# BMS_Rev2_logic_B.net
KiCad netlist of a schematic drawn in EAGLE
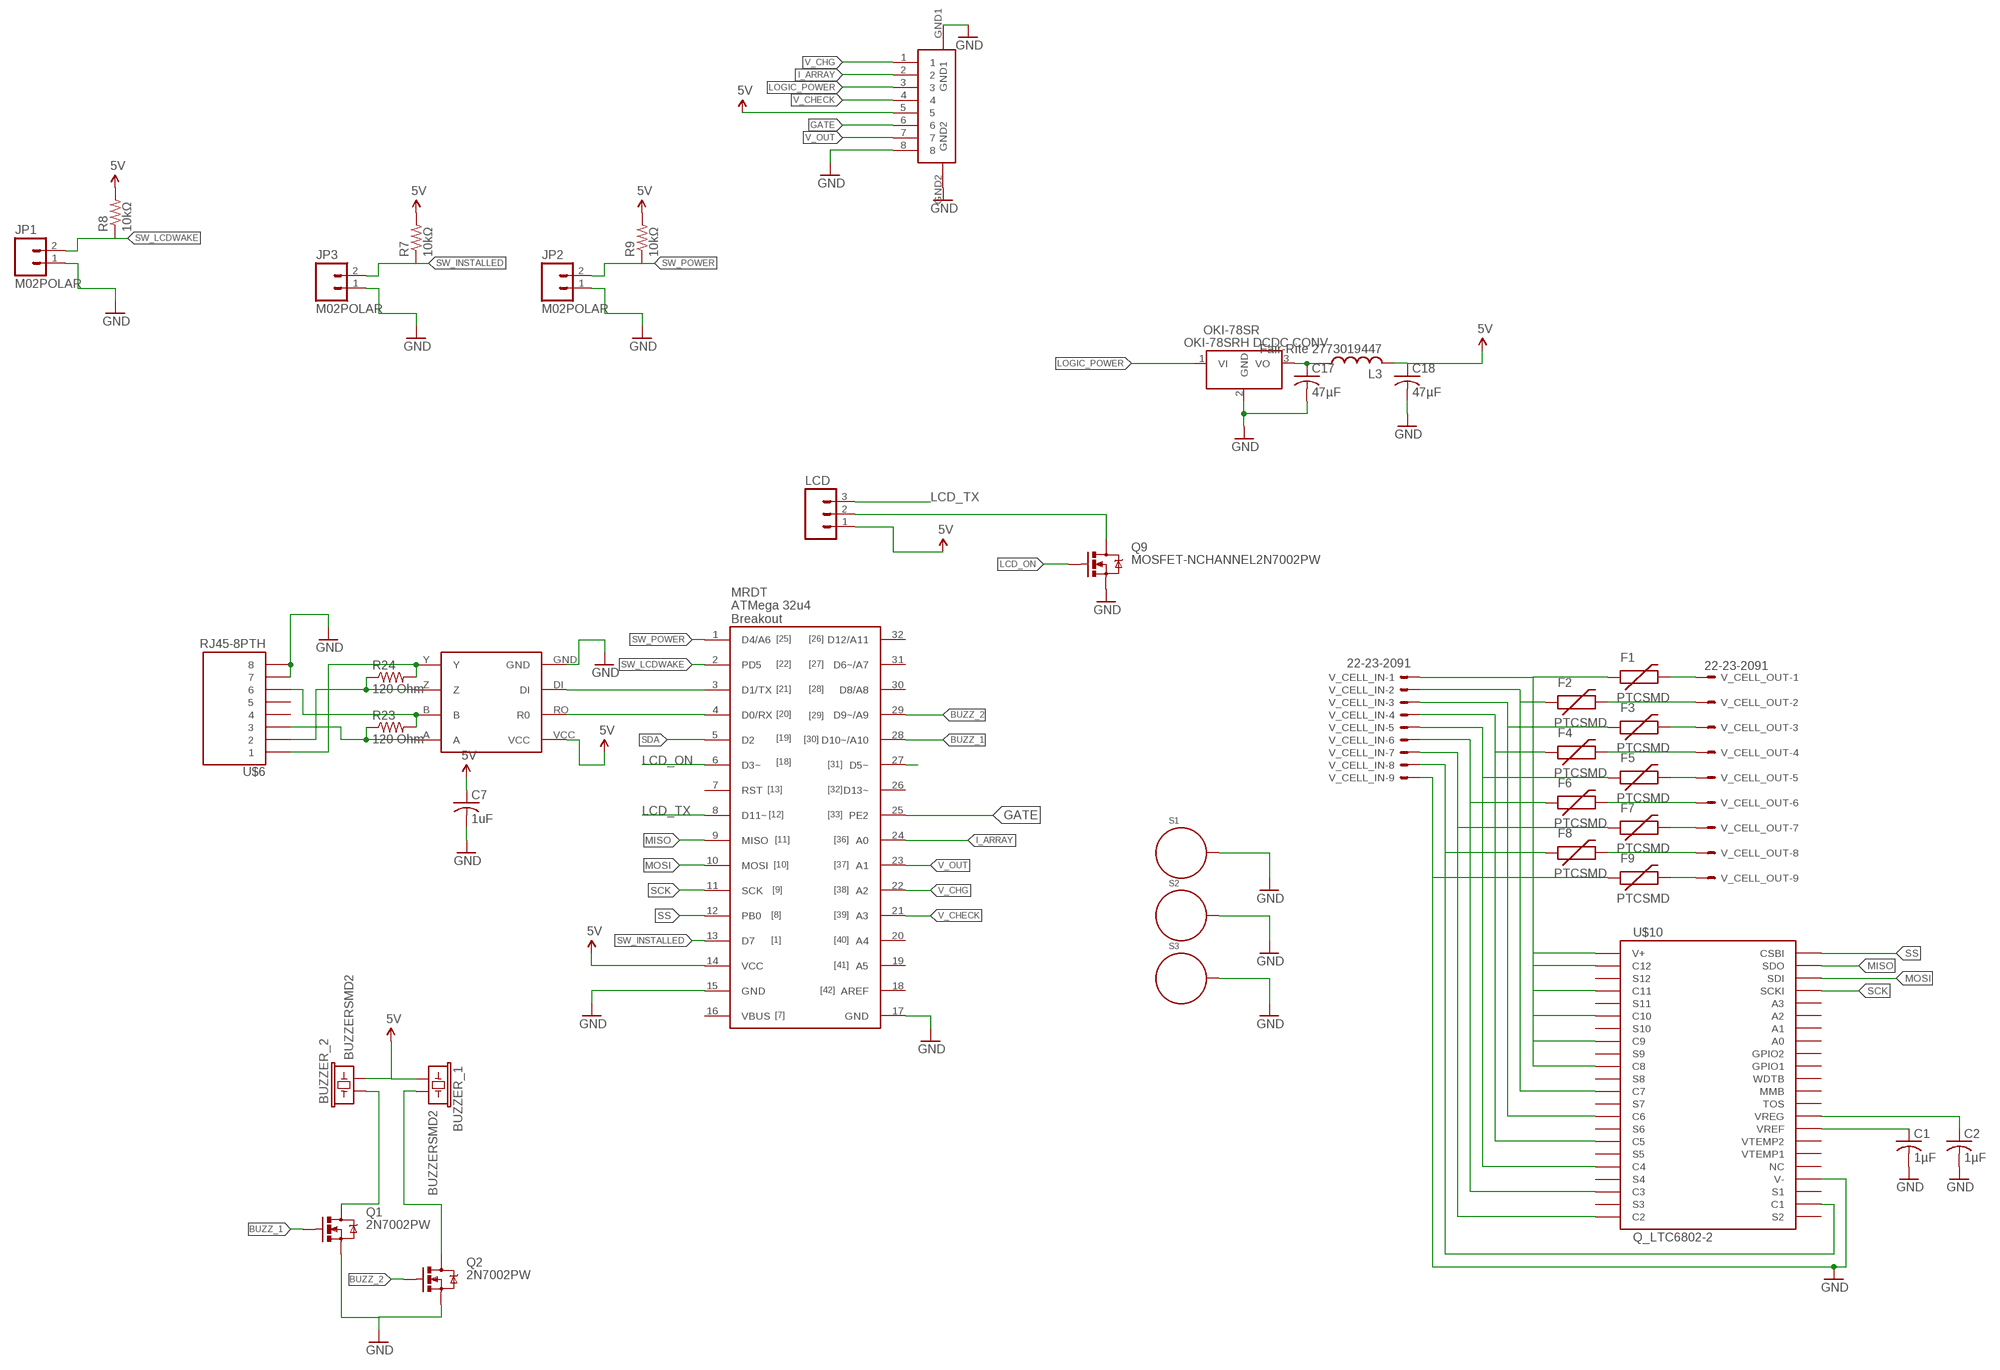
[diagram p0: schematic, sheet 1]

(export (version "E")
  (design (tool "Eeschema 10.0.6"))
  (components
    (comp (ref "BUZZER_1")
      (value "BUZZERSMD2")
      (footprint "eagle-import:BUZZER-CCV")
      (libsource (lib "eagle-import") (part "BUZZERSMD2"))
    )
    (comp (ref "BUZZER_2")
      (value "BUZZERSMD2")
      (footprint "eagle-import:BUZZER-CCV")
      (libsource (lib "eagle-import") (part "BUZZERSMD2"))
    )
    (comp (ref "C1")
      (value "1µF")
      (footprint "eagle-import:C1206")
      (libsource (lib "eagle-import") (part "C-USC1206"))
    )
    (comp (ref "C2")
      (value "1µF")
      (footprint "eagle-import:C1206")
      (libsource (lib "eagle-import") (part "C-USC1206"))
    )
    (comp (ref "C7")
      (value "1uF")
      (footprint "eagle-import:C1206")
      (libsource (lib "eagle-import") (part "C-USC1206"))
    )
    (comp (ref "C17")
      (value "47µF")
      (footprint "eagle-import:C1206")
      (libsource (lib "eagle-import") (part "C-USC1206"))
    )
    (comp (ref "C18")
      (value "47µF")
      (footprint "eagle-import:C1206")
      (libsource (lib "eagle-import") (part "C-USC1206"))
    )
    (comp (ref "F1")
      (value "PTCSMD")
      (footprint "eagle-import:PTC-1206")
      (libsource (lib "eagle-import") (part "PTCSMD"))
    )
    (comp (ref "F2")
      (value "PTCSMD")
      (footprint "eagle-import:PTC-1206")
      (libsource (lib "eagle-import") (part "PTCSMD"))
    )
    (comp (ref "F3")
      (value "PTCSMD")
      (footprint "eagle-import:PTC-1206")
      (libsource (lib "eagle-import") (part "PTCSMD"))
    )
    (comp (ref "F4")
      (value "PTCSMD")
      (footprint "eagle-import:PTC-1206")
      (libsource (lib "eagle-import") (part "PTCSMD"))
    )
    (comp (ref "F5")
      (value "PTCSMD")
      (footprint "eagle-import:PTC-1206")
      (libsource (lib "eagle-import") (part "PTCSMD"))
    )
    (comp (ref "F6")
      (value "PTCSMD")
      (footprint "eagle-import:PTC-1206")
      (libsource (lib "eagle-import") (part "PTCSMD"))
    )
    (comp (ref "F7")
      (value "PTCSMD")
      (footprint "eagle-import:PTC-1206")
      (libsource (lib "eagle-import") (part "PTCSMD"))
    )
    (comp (ref "F8")
      (value "PTCSMD")
      (footprint "eagle-import:PTC-1206")
      (libsource (lib "eagle-import") (part "PTCSMD"))
    )
    (comp (ref "F9")
      (value "PTCSMD")
      (footprint "eagle-import:PTC-1206")
      (libsource (lib "eagle-import") (part "PTCSMD"))
    )
    (comp (ref "JP1")
      (value "M02POLAR")
      (footprint "eagle-import:MOLEX-1X2")
      (libsource (lib "eagle-import") (part "M02POLAR"))
    )
    (comp (ref "JP2")
      (value "M02POLAR")
      (footprint "eagle-import:MOLEX-1X2")
      (libsource (lib "eagle-import") (part "M02POLAR"))
    )
    (comp (ref "JP3")
      (value "M02POLAR")
      (footprint "eagle-import:MOLEX-1X2")
      (libsource (lib "eagle-import") (part "M02POLAR"))
    )
    (comp (ref "L3")
      (value "Fair-Rite 2773019447")
      (footprint "eagle-import:L4532M")
      (libsource (lib "eagle-import") (part "L-USL4532C"))
    )
    (comp (ref "LCD")
      (value "M03POLAR")
      (footprint "eagle-import:MOLEX-1X3")
      (libsource (lib "eagle-import") (part "M03POLAR"))
    )
    (comp (ref "OKI-78SR")
      (value "Q_OKI-78SR")
      (footprint "eagle-import:OKI-78SRH")
      (libsource (lib "eagle-import") (part "Q_OKI-78SR"))
    )
    (comp (ref "Q1")
      (value "2N7002PW")
      (footprint "eagle-import:SOT323")
      (libsource (lib "eagle-import") (part "MOSFET-NCHANNEL2N7002PW"))
    )
    (comp (ref "Q2")
      (value "2N7002PW")
      (footprint "eagle-import:SOT323")
      (libsource (lib "eagle-import") (part "MOSFET-NCHANNEL2N7002PW"))
    )
    (comp (ref "Q9")
      (value "MOSFET-NCHANNEL2N7002PW")
      (footprint "eagle-import:SOT323")
      (libsource (lib "eagle-import") (part "MOSFET-NCHANNEL2N7002PW"))
    )
    (comp (ref "R7")
      (value "10kΩ")
      (footprint "eagle-import:R1206")
      (libsource (lib "eagle-import") (part "R-US_R1206"))
    )
    (comp (ref "R8")
      (value "10kΩ")
      (footprint "eagle-import:R1206")
      (libsource (lib "eagle-import") (part "R-US_R1206"))
    )
    (comp (ref "R9")
      (value "10kΩ")
      (footprint "eagle-import:R1206")
      (libsource (lib "eagle-import") (part "R-US_R1206"))
    )
    (comp (ref "R23")
      (value "120 Ohm")
      (footprint "eagle-import:1206")
      (libsource (lib "eagle-import") (part "RESISTOR1206"))
    )
    (comp (ref "R24")
      (value "120 Ohm")
      (footprint "eagle-import:1206")
      (libsource (lib "eagle-import") (part "RESISTOR1206"))
    )
    (comp (ref "S1")
      (value "STANDOFF_ELECTRICAL")
      (footprint "eagle-import:STANDOFF-ELECTRICAL")
      (libsource (lib "eagle-import") (part "STANDOFF_ELECTRICAL"))
    )
    (comp (ref "S2")
      (value "STANDOFF_ELECTRICAL")
      (footprint "eagle-import:STANDOFF-ELECTRICAL")
      (libsource (lib "eagle-import") (part "STANDOFF_ELECTRICAL"))
    )
    (comp (ref "S3")
      (value "STANDOFF_ELECTRICAL")
      (footprint "eagle-import:STANDOFF-ELECTRICAL")
      (libsource (lib "eagle-import") (part "STANDOFF_ELECTRICAL"))
    )
    (comp (ref "U$1")
      (value "8POS_LOGIC")
      (footprint "eagle-import:LOGIC_CONNECT")
      (libsource (lib "eagle-import") (part "8POS_LOGIC"))
    )
    (comp (ref "U$3")
      (value "32U4_BREAKOUT")
      (footprint "eagle-import:32U4_MCU_DIP")
      (libsource (lib "eagle-import") (part "32U4_BREAKOUT"))
    )
    (comp (ref "U$6")
      (value "RJ45-8PTH")
      (footprint "eagle-import:RJ45-8")
      (libsource (lib "eagle-import") (part "RJ45-8PTH"))
    )
    (comp (ref "U$9")
      (value "MAX3077")
      (footprint "eagle-import:MAX3070E")
      (libsource (lib "eagle-import") (part "MAX3077"))
    )
    (comp (ref "U$10")
      (value "Q_LTC6802-2")
      (footprint "eagle-import:SSOP44")
      (libsource (lib "eagle-import") (part "Q_LTC6802-2"))
    )
    (comp (ref "V_CELL_IN")
      (value "22-23-2091")
      (footprint "eagle-import:22-23-2091")
      (fields (field (name "MF") "MOLEX"))
      (libsource (lib "eagle-import") (part "22-23-2091"))
    )
    (comp (ref "V_CELL_OUT")
      (value "22-23-2091")
      (footprint "eagle-import:22-23-2091")
      (fields (field (name "MF") "MOLEX"))
      (libsource (lib "eagle-import") (part "22-23-2091"))
    )
  )
  (nets
    (net (code "1") (name "/LCD_TX") (class "Default")
      (node (ref "LCD") (pin "3") (pinfunction "3_3") (pintype "passive"))
      (node (ref "U$3") (pin "8") (pinfunction "D11~{}_8") (pintype "bidirectional"))
    )
    (net (code "2") (name "5V") (class "Default")
      (node (ref "BUZZER_1") (pin "+") (pinfunction "1_+") (pintype "passive"))
      (node (ref "BUZZER_2") (pin "-") (pinfunction "2_-") (pintype "passive"))
      (node (ref "C18") (pin "1") (pinfunction "1_1") (pintype "passive"))
      (node (ref "C7") (pin "1") (pinfunction "1_1") (pintype "passive"))
      (node (ref "L3") (pin "2") (pinfunction "2_2") (pintype "passive"))
      (node (ref "LCD") (pin "1") (pinfunction "1_1") (pintype "passive"))
      (node (ref "R7") (pin "2") (pinfunction "2_2") (pintype "passive"))
      (node (ref "R8") (pin "2") (pinfunction "2_2") (pintype "passive"))
      (node (ref "R9") (pin "2") (pinfunction "2_2") (pintype "passive"))
      (node (ref "U$1") (pin "5") (pinfunction "5_5") (pintype "bidirectional"))
      (node (ref "U$3") (pin "14") (pinfunction "VCC_14") (pintype "bidirectional"))
      (node (ref "U$9") (pin "VCC") (pinfunction "VCC_VCC") (pintype "bidirectional"))
    )
    (net (code "3") (name "BUZZ_1") (class "Default")
      (node (ref "Q1") (pin "1") (pinfunction "G_1") (pintype "passive"))
      (node (ref "U$3") (pin "28") (pinfunction "D10~{/A10}_28") (pintype "bidirectional"))
    )
    (net (code "4") (name "BUZZ_2") (class "Default")
      (node (ref "Q2") (pin "1") (pinfunction "G_1") (pintype "passive"))
      (node (ref "U$3") (pin "29") (pinfunction "D9~{/A9}_29") (pintype "bidirectional"))
    )
    (net (code "5") (name "GATE") (class "Default")
      (node (ref "U$1") (pin "6") (pinfunction "6_6") (pintype "bidirectional"))
      (node (ref "U$3") (pin "25") (pinfunction "PE2_25") (pintype "bidirectional"))
    )
    (net (code "6") (name "GND") (class "Default")
      (node (ref "C1") (pin "2") (pinfunction "2_2") (pintype "passive"))
      (node (ref "C17") (pin "2") (pinfunction "2_2") (pintype "passive"))
      (node (ref "C18") (pin "2") (pinfunction "2_2") (pintype "passive"))
      (node (ref "C2") (pin "2") (pinfunction "2_2") (pintype "passive"))
      (node (ref "C7") (pin "2") (pinfunction "2_2") (pintype "passive"))
      (node (ref "F9") (pin "1") (pinfunction "1_1") (pintype "bidirectional"))
      (node (ref "JP1") (pin "1") (pinfunction "1_1") (pintype "passive"))
      (node (ref "JP2") (pin "1") (pinfunction "1_1") (pintype "passive"))
      (node (ref "JP3") (pin "1") (pinfunction "1_1") (pintype "passive"))
      (node (ref "OKI-78SR") (pin "2") (pinfunction "GND_2") (pintype "bidirectional"))
      (node (ref "Q1") (pin "2") (pinfunction "S_2") (pintype "passive"))
      (node (ref "Q2") (pin "2") (pinfunction "S_2") (pintype "passive"))
      (node (ref "Q9") (pin "2") (pinfunction "S_2") (pintype "passive"))
      (node (ref "S1") (pin "P1") (pinfunction "P$1_P1") (pintype "bidirectional"))
      (node (ref "S2") (pin "P1") (pinfunction "P$1_P1") (pintype "bidirectional"))
      (node (ref "S3") (pin "P1") (pinfunction "P$1_P1") (pintype "bidirectional"))
      (node (ref "U$1") (pin "8") (pinfunction "8_8") (pintype "bidirectional"))
      (node (ref "U$1") (pin "GND1") (pinfunction "GND1_GND1") (pintype "bidirectional"))
      (node (ref "U$1") (pin "GND2") (pinfunction "GND2_GND2") (pintype "bidirectional"))
      (node (ref "U$10") (pin "26") (pinfunction "V-_26") (pintype "bidirectional"))
      (node (ref "U$3") (pin "15") (pinfunction "GND_15") (pintype "bidirectional"))
      (node (ref "U$3") (pin "17") (pinfunction "GND_17") (pintype "bidirectional"))
      (node (ref "U$6") (pin "7") (pinfunction "7_7") (pintype "bidirectional"))
      (node (ref "U$6") (pin "8") (pinfunction "8_8") (pintype "bidirectional"))
      (node (ref "U$9") (pin "GND") (pinfunction "GND_GND") (pintype "bidirectional"))
      (node (ref "V_CELL_IN") (pin "9") (pinfunction "S_9") (pintype "passive"))
    )
    (net (code "7") (name "I_ARRAY") (class "Default")
      (node (ref "U$1") (pin "2") (pinfunction "2_2") (pintype "bidirectional"))
      (node (ref "U$3") (pin "24") (pinfunction "A0_24") (pintype "bidirectional"))
    )
    (net (code "8") (name "LCD_ON") (class "Default")
      (node (ref "Q9") (pin "1") (pinfunction "G_1") (pintype "passive"))
      (node (ref "U$3") (pin "6") (pinfunction "D3~{}_6") (pintype "bidirectional"))
    )
    (net (code "9") (name "LOGIC_POWER") (class "Default")
      (node (ref "OKI-78SR") (pin "1") (pinfunction "VI_1") (pintype "bidirectional"))
      (node (ref "U$1") (pin "3") (pinfunction "3_3") (pintype "bidirectional"))
    )
    (net (code "10") (name "MISO") (class "Default")
      (node (ref "U$10") (pin "43") (pinfunction "SDO_43") (pintype "bidirectional"))
      (node (ref "U$3") (pin "9") (pinfunction "MISO_9") (pintype "bidirectional"))
    )
    (net (code "11") (name "MOSI") (class "Default")
      (node (ref "U$10") (pin "42") (pinfunction "SDI_42") (pintype "bidirectional"))
      (node (ref "U$3") (pin "10") (pinfunction "MOSI_10") (pintype "bidirectional"))
    )
    (net (code "12") (name "Net-(BUZZER_1-2)") (class "Default")
      (node (ref "BUZZER_1") (pin "-") (pinfunction "2_-") (pintype "passive"))
      (node (ref "Q2") (pin "3") (pinfunction "D_3") (pintype "passive"))
    )
    (net (code "13") (name "Net-(BUZZER_2-1)") (class "Default")
      (node (ref "BUZZER_2") (pin "+") (pinfunction "1_+") (pintype "passive"))
      (node (ref "Q1") (pin "3") (pinfunction "D_3") (pintype "passive"))
    )
    (net (code "14") (name "Net-(OKI-78SR-VO)") (class "Default")
      (node (ref "C17") (pin "1") (pinfunction "1_1") (pintype "passive"))
      (node (ref "L3") (pin "1") (pinfunction "1_1") (pintype "passive"))
      (node (ref "OKI-78SR") (pin "3") (pinfunction "VO_3") (pintype "bidirectional"))
    )
    (net (code "15") (name "Net-(Q9-D)") (class "Default")
      (node (ref "LCD") (pin "2") (pinfunction "2_2") (pintype "passive"))
      (node (ref "Q9") (pin "3") (pinfunction "D_3") (pintype "passive"))
    )
    (net (code "16") (name "Net-(R23-Pad1)") (class "Default")
      (node (ref "R23") (pin "1") (pinfunction "1_1") (pintype "passive"))
      (node (ref "U$6") (pin "3") (pinfunction "3_3") (pintype "bidirectional"))
      (node (ref "U$9") (pin "A") (pinfunction "A_A") (pintype "bidirectional"))
    )
    (net (code "17") (name "Net-(R23-Pad2)") (class "Default")
      (node (ref "R23") (pin "2") (pinfunction "2_2") (pintype "passive"))
      (node (ref "U$6") (pin "6") (pinfunction "6_6") (pintype "bidirectional"))
      (node (ref "U$9") (pin "B") (pinfunction "B_B") (pintype "bidirectional"))
    )
    (net (code "18") (name "Net-(R24-Pad1)") (class "Default")
      (node (ref "R24") (pin "1") (pinfunction "1_1") (pintype "passive"))
      (node (ref "U$6") (pin "2") (pinfunction "2_2") (pintype "bidirectional"))
      (node (ref "U$9") (pin "Z") (pinfunction "Z_Z") (pintype "bidirectional"))
    )
    (net (code "19") (name "Net-(R24-Pad2)") (class "Default")
      (node (ref "R24") (pin "2") (pinfunction "2_2") (pintype "passive"))
      (node (ref "U$6") (pin "1") (pinfunction "1_1") (pintype "bidirectional"))
      (node (ref "U$9") (pin "Y") (pinfunction "Y_Y") (pintype "bidirectional"))
    )
    (net (code "20") (name "Net-(U$3-D0{slash}RX)") (class "Default")
      (node (ref "U$3") (pin "4") (pinfunction "D0/RX_4") (pintype "bidirectional"))
      (node (ref "U$9") (pin "RO") (pinfunction "R0_RO") (pintype "bidirectional"))
    )
    (net (code "21") (name "Net-(U$3-D1{slash}TX)") (class "Default")
      (node (ref "U$3") (pin "3") (pinfunction "D1/TX_3") (pintype "bidirectional"))
      (node (ref "U$9") (pin "DI") (pinfunction "DI_DI") (pintype "bidirectional"))
    )
    (net (code "22") (name "Net-(U$10-C1)") (class "Default")
      (node (ref "F8") (pin "1") (pinfunction "1_1") (pintype "bidirectional"))
      (node (ref "U$10") (pin "24") (pinfunction "C1_24") (pintype "bidirectional"))
      (node (ref "V_CELL_IN") (pin "8") (pinfunction "S_8") (pintype "passive"))
    )
    (net (code "23") (name "Net-(U$10-C2)") (class "Default")
      (node (ref "F7") (pin "1") (pinfunction "1_1") (pintype "bidirectional"))
      (node (ref "U$10") (pin "22") (pinfunction "C2_22") (pintype "bidirectional"))
      (node (ref "V_CELL_IN") (pin "7") (pinfunction "S_7") (pintype "passive"))
    )
    (net (code "24") (name "Net-(U$10-C3)") (class "Default")
      (node (ref "F6") (pin "1") (pinfunction "1_1") (pintype "bidirectional"))
      (node (ref "U$10") (pin "20") (pinfunction "C3_20") (pintype "bidirectional"))
      (node (ref "V_CELL_IN") (pin "6") (pinfunction "S_6") (pintype "passive"))
    )
    (net (code "25") (name "Net-(U$10-C4)") (class "Default")
      (node (ref "F5") (pin "1") (pinfunction "1_1") (pintype "bidirectional"))
      (node (ref "U$10") (pin "18") (pinfunction "C4_18") (pintype "bidirectional"))
      (node (ref "V_CELL_IN") (pin "5") (pinfunction "S_5") (pintype "passive"))
    )
    (net (code "26") (name "Net-(U$10-C5)") (class "Default")
      (node (ref "F4") (pin "1") (pinfunction "1_1") (pintype "bidirectional"))
      (node (ref "U$10") (pin "16") (pinfunction "C5_16") (pintype "bidirectional"))
      (node (ref "V_CELL_IN") (pin "4") (pinfunction "S_4") (pintype "passive"))
    )
    (net (code "27") (name "Net-(U$10-C6)") (class "Default")
      (node (ref "F3") (pin "1") (pinfunction "1_1") (pintype "bidirectional"))
      (node (ref "U$10") (pin "14") (pinfunction "C6_14") (pintype "bidirectional"))
      (node (ref "V_CELL_IN") (pin "3") (pinfunction "S_3") (pintype "passive"))
    )
    (net (code "28") (name "Net-(U$10-C7)") (class "Default")
      (node (ref "F2") (pin "1") (pinfunction "1_1") (pintype "bidirectional"))
      (node (ref "U$10") (pin "12") (pinfunction "C7_12") (pintype "bidirectional"))
      (node (ref "V_CELL_IN") (pin "2") (pinfunction "S_2") (pintype "passive"))
    )
    (net (code "29") (name "Net-(U$10-C10)") (class "Default")
      (node (ref "F1") (pin "1") (pinfunction "1_1") (pintype "bidirectional"))
      (node (ref "U$10") (pin "1") (pinfunction "V+_1") (pintype "bidirectional"))
      (node (ref "U$10") (pin "10") (pinfunction "C8_10") (pintype "bidirectional"))
      (node (ref "U$10") (pin "2") (pinfunction "C12_2") (pintype "bidirectional"))
      (node (ref "U$10") (pin "4") (pinfunction "C11_4") (pintype "bidirectional"))
      (node (ref "U$10") (pin "6") (pinfunction "C10_6") (pintype "bidirectional"))
      (node (ref "U$10") (pin "8") (pinfunction "C9_8") (pintype "bidirectional"))
      (node (ref "V_CELL_IN") (pin "1") (pinfunction "S_1") (pintype "passive"))
    )
    (net (code "30") (name "Net-(U$10-VREF)") (class "Default")
      (node (ref "C1") (pin "1") (pinfunction "1_1") (pintype "passive"))
      (node (ref "U$10") (pin "30") (pinfunction "VREF_30") (pintype "bidirectional"))
    )
    (net (code "31") (name "Net-(U$10-VREG)") (class "Default")
      (node (ref "C2") (pin "1") (pinfunction "1_1") (pintype "passive"))
      (node (ref "U$10") (pin "31") (pinfunction "VREG_31") (pintype "bidirectional"))
    )
    (net (code "32") (name "Net-(V_CELL_OUTA-S)") (class "Default")
      (node (ref "F1") (pin "2") (pinfunction "2_2") (pintype "bidirectional"))
      (node (ref "V_CELL_OUT") (pin "1") (pinfunction "S_1") (pintype "passive"))
    )
    (net (code "33") (name "Net-(V_CELL_OUTB-S)") (class "Default")
      (node (ref "F2") (pin "2") (pinfunction "2_2") (pintype "bidirectional"))
      (node (ref "V_CELL_OUT") (pin "2") (pinfunction "S_2") (pintype "passive"))
    )
    (net (code "34") (name "Net-(V_CELL_OUTC-S)") (class "Default")
      (node (ref "F3") (pin "2") (pinfunction "2_2") (pintype "bidirectional"))
      (node (ref "V_CELL_OUT") (pin "3") (pinfunction "S_3") (pintype "passive"))
    )
    (net (code "35") (name "Net-(V_CELL_OUTD-S)") (class "Default")
      (node (ref "F4") (pin "2") (pinfunction "2_2") (pintype "bidirectional"))
      (node (ref "V_CELL_OUT") (pin "4") (pinfunction "S_4") (pintype "passive"))
    )
    (net (code "36") (name "Net-(V_CELL_OUTE-S)") (class "Default")
      (node (ref "F5") (pin "2") (pinfunction "2_2") (pintype "bidirectional"))
      (node (ref "V_CELL_OUT") (pin "5") (pinfunction "S_5") (pintype "passive"))
    )
    (net (code "37") (name "Net-(V_CELL_OUTF-S)") (class "Default")
      (node (ref "F6") (pin "2") (pinfunction "2_2") (pintype "bidirectional"))
      (node (ref "V_CELL_OUT") (pin "6") (pinfunction "S_6") (pintype "passive"))
    )
    (net (code "38") (name "Net-(V_CELL_OUTG-S)") (class "Default")
      (node (ref "F7") (pin "2") (pinfunction "2_2") (pintype "bidirectional"))
      (node (ref "V_CELL_OUT") (pin "7") (pinfunction "S_7") (pintype "passive"))
    )
    (net (code "39") (name "Net-(V_CELL_OUTH-S)") (class "Default")
      (node (ref "F8") (pin "2") (pinfunction "2_2") (pintype "bidirectional"))
      (node (ref "V_CELL_OUT") (pin "8") (pinfunction "S_8") (pintype "passive"))
    )
    (net (code "40") (name "Net-(V_CELL_OUTI-S)") (class "Default")
      (node (ref "F9") (pin "2") (pinfunction "2_2") (pintype "bidirectional"))
      (node (ref "V_CELL_OUT") (pin "9") (pinfunction "S_9") (pintype "passive"))
    )
    (net (code "41") (name "SCK") (class "Default")
      (node (ref "U$10") (pin "41") (pinfunction "SCKI_41") (pintype "bidirectional"))
      (node (ref "U$3") (pin "11") (pinfunction "SCK_11") (pintype "bidirectional"))
    )
    (net (code "42") (name "SDA") (class "Default")
      (node (ref "U$3") (pin "5") (pinfunction "D2_5") (pintype "bidirectional"))
    )
    (net (code "43") (name "SS") (class "Default")
      (node (ref "U$10") (pin "44") (pinfunction "CSBI_44") (pintype "bidirectional"))
      (node (ref "U$3") (pin "12") (pinfunction "PB0_12") (pintype "bidirectional"))
    )
    (net (code "44") (name "SW_INSTALLED") (class "Default")
      (node (ref "JP3") (pin "2") (pinfunction "2_2") (pintype "passive"))
      (node (ref "R7") (pin "1") (pinfunction "1_1") (pintype "passive"))
      (node (ref "U$3") (pin "13") (pinfunction "D7_13") (pintype "bidirectional"))
    )
    (net (code "45") (name "SW_LCDWAKE") (class "Default")
      (node (ref "JP1") (pin "2") (pinfunction "2_2") (pintype "passive"))
      (node (ref "R8") (pin "1") (pinfunction "1_1") (pintype "passive"))
      (node (ref "U$3") (pin "2") (pinfunction "PD5_2") (pintype "bidirectional"))
    )
    (net (code "46") (name "SW_POWER") (class "Default")
      (node (ref "JP2") (pin "2") (pinfunction "2_2") (pintype "passive"))
      (node (ref "R9") (pin "1") (pinfunction "1_1") (pintype "passive"))
      (node (ref "U$3") (pin "1") (pinfunction "D4/A6_1") (pintype "bidirectional"))
    )
    (net (code "47") (name "V_CHECK") (class "Default")
      (node (ref "U$1") (pin "4") (pinfunction "4_4") (pintype "bidirectional"))
      (node (ref "U$3") (pin "21") (pinfunction "A3_21") (pintype "bidirectional"))
    )
    (net (code "48") (name "V_CHG") (class "Default")
      (node (ref "U$1") (pin "1") (pinfunction "1_1") (pintype "bidirectional"))
      (node (ref "U$3") (pin "22") (pinfunction "A2_22") (pintype "bidirectional"))
    )
    (net (code "49") (name "V_OUT") (class "Default")
      (node (ref "U$1") (pin "7") (pinfunction "7_7") (pintype "bidirectional"))
      (node (ref "U$3") (pin "23") (pinfunction "A1_23") (pintype "bidirectional"))
    )
    (net (code "50") (name "unconnected-(U$3-A4-Pad20)") (class "Default")
      (node (ref "U$3") (pin "20") (pinfunction "A4_20") (pintype "bidirectional"))
    )
    (net (code "51") (name "unconnected-(U$3-A5-Pad19)") (class "Default")
      (node (ref "U$3") (pin "19") (pinfunction "A5_19") (pintype "bidirectional"))
    )
    (net (code "52") (name "unconnected-(U$3-AREF-Pad18)") (class "Default")
      (node (ref "U$3") (pin "18") (pinfunction "AREF_18") (pintype "bidirectional"))
    )
    (net (code "53") (name "unconnected-(U$3-D5~{}-Pad27)") (class "Default")
      (node (ref "U$3") (pin "27") (pinfunction "D5~{}_27") (pintype "bidirectional"))
    )
    (net (code "54") (name "unconnected-(U$3-D6~{{slash}A7}-Pad31)") (class "Default")
      (node (ref "U$3") (pin "31") (pinfunction "D6~{/A7}_31") (pintype "bidirectional"))
    )
    (net (code "55") (name "unconnected-(U$3-D8{slash}A8-Pad30)") (class "Default")
      (node (ref "U$3") (pin "30") (pinfunction "D8/A8_30") (pintype "bidirectional"))
    )
    (net (code "56") (name "unconnected-(U$3-D12{slash}A11-Pad32)") (class "Default")
      (node (ref "U$3") (pin "32") (pinfunction "D12/A11_32") (pintype "bidirectional"))
    )
    (net (code "57") (name "unconnected-(U$3-D13~{}-Pad26)") (class "Default")
      (node (ref "U$3") (pin "26") (pinfunction "D13~{}_26") (pintype "bidirectional"))
    )
    (net (code "58") (name "unconnected-(U$3-RST-Pad7)") (class "Default")
      (node (ref "U$3") (pin "7") (pinfunction "RST_7") (pintype "bidirectional"))
    )
    (net (code "59") (name "unconnected-(U$3-VBUS-Pad16)") (class "Default")
      (node (ref "U$3") (pin "16") (pinfunction "VBUS_16") (pintype "bidirectional"))
    )
    (net (code "60") (name "unconnected-(U$6-Pad4)") (class "Default")
      (node (ref "U$6") (pin "4") (pinfunction "4_4") (pintype "bidirectional"))
    )
    (net (code "61") (name "unconnected-(U$6-Pad5)") (class "Default")
      (node (ref "U$6") (pin "5") (pinfunction "5_5") (pintype "bidirectional"))
    )
    (net (code "62") (name "unconnected-(U$10-A0-Pad37)") (class "Default")
      (node (ref "U$10") (pin "37") (pinfunction "A0_37") (pintype "bidirectional"))
    )
    (net (code "63") (name "unconnected-(U$10-A1-Pad38)") (class "Default")
      (node (ref "U$10") (pin "38") (pinfunction "A1_38") (pintype "bidirectional"))
    )
    (net (code "64") (name "unconnected-(U$10-A2-Pad39)") (class "Default")
      (node (ref "U$10") (pin "39") (pinfunction "A2_39") (pintype "bidirectional"))
    )
    (net (code "65") (name "unconnected-(U$10-A3-Pad40)") (class "Default")
      (node (ref "U$10") (pin "40") (pinfunction "A3_40") (pintype "bidirectional"))
    )
    (net (code "66") (name "unconnected-(U$10-GPIO1-Pad35)") (class "Default")
      (node (ref "U$10") (pin "35") (pinfunction "GPIO1_35") (pintype "bidirectional"))
    )
    (net (code "67") (name "unconnected-(U$10-GPIO2-Pad36)") (class "Default")
      (node (ref "U$10") (pin "36") (pinfunction "GPIO2_36") (pintype "bidirectional"))
    )
    (net (code "68") (name "unconnected-(U$10-MMB-Pad33)") (class "Default")
      (node (ref "U$10") (pin "33") (pinfunction "MMB_33") (pintype "bidirectional"))
    )
    (net (code "69") (name "unconnected-(U$10-NC-Pad27)") (class "Default")
      (node (ref "U$10") (pin "27") (pinfunction "NC_27") (pintype "bidirectional"))
    )
    (net (code "70") (name "unconnected-(U$10-S1-Pad25)") (class "Default")
      (node (ref "U$10") (pin "25") (pinfunction "S1_25") (pintype "bidirectional"))
    )
    (net (code "71") (name "unconnected-(U$10-S2-Pad23)") (class "Default")
      (node (ref "U$10") (pin "23") (pinfunction "S2_23") (pintype "bidirectional"))
    )
    (net (code "72") (name "unconnected-(U$10-S3-Pad21)") (class "Default")
      (node (ref "U$10") (pin "21") (pinfunction "S3_21") (pintype "bidirectional"))
    )
    (net (code "73") (name "unconnected-(U$10-S4-Pad19)") (class "Default")
      (node (ref "U$10") (pin "19") (pinfunction "S4_19") (pintype "bidirectional"))
    )
    (net (code "74") (name "unconnected-(U$10-S5-Pad17)") (class "Default")
      (node (ref "U$10") (pin "17") (pinfunction "S5_17") (pintype "bidirectional"))
    )
    (net (code "75") (name "unconnected-(U$10-S6-Pad15)") (class "Default")
      (node (ref "U$10") (pin "15") (pinfunction "S6_15") (pintype "bidirectional"))
    )
    (net (code "76") (name "unconnected-(U$10-S7-Pad13)") (class "Default")
      (node (ref "U$10") (pin "13") (pinfunction "S7_13") (pintype "bidirectional"))
    )
    (net (code "77") (name "unconnected-(U$10-S8-Pad11)") (class "Default")
      (node (ref "U$10") (pin "11") (pinfunction "S8_11") (pintype "bidirectional"))
    )
    (net (code "78") (name "unconnected-(U$10-S9-Pad9)") (class "Default")
      (node (ref "U$10") (pin "9") (pinfunction "S9_9") (pintype "bidirectional"))
    )
    (net (code "79") (name "unconnected-(U$10-S10-Pad7)") (class "Default")
      (node (ref "U$10") (pin "7") (pinfunction "S10_7") (pintype "bidirectional"))
    )
    (net (code "80") (name "unconnected-(U$10-S11-Pad5)") (class "Default")
      (node (ref "U$10") (pin "5") (pinfunction "S11_5") (pintype "bidirectional"))
    )
    (net (code "81") (name "unconnected-(U$10-S12-Pad3)") (class "Default")
      (node (ref "U$10") (pin "3") (pinfunction "S12_3") (pintype "bidirectional"))
    )
    (net (code "82") (name "unconnected-(U$10-TOS-Pad32)") (class "Default")
      (node (ref "U$10") (pin "32") (pinfunction "TOS_32") (pintype "bidirectional"))
    )
    (net (code "83") (name "unconnected-(U$10-VTEMP1-Pad28)") (class "Default")
      (node (ref "U$10") (pin "28") (pinfunction "VTEMP1_28") (pintype "bidirectional"))
    )
    (net (code "84") (name "unconnected-(U$10-VTEMP2-Pad29)") (class "Default")
      (node (ref "U$10") (pin "29") (pinfunction "VTEMP2_29") (pintype "bidirectional"))
    )
    (net (code "85") (name "unconnected-(U$10-WDTB-Pad34)") (class "Default")
      (node (ref "U$10") (pin "34") (pinfunction "WDTB_34") (pintype "bidirectional"))
    )
  )
)
